# DigitalLabBoard_Stepper.net
KiCad netlist of a schematic drawn in Altium Designer
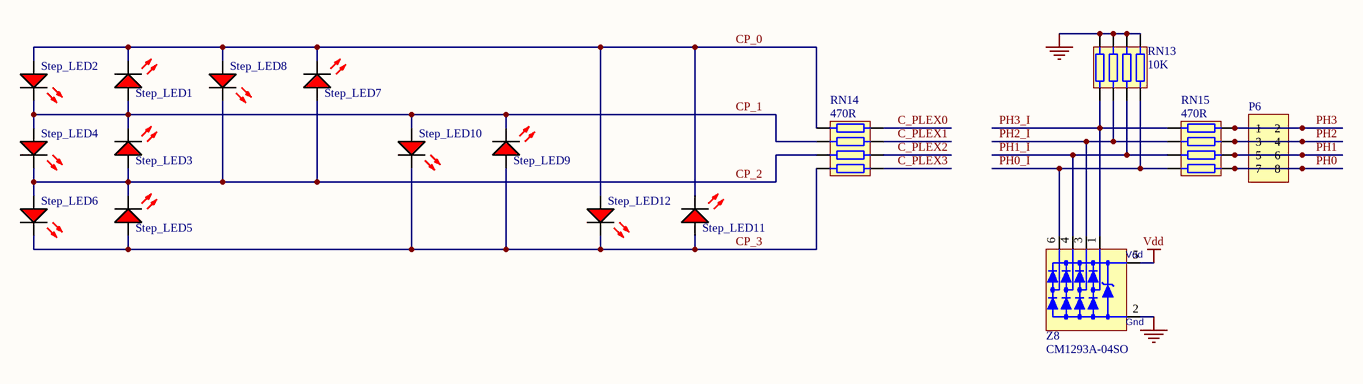
[diagram p0: DigitalLabBoard_Stepper.SchDoc]

(export (version "E")
  (design (tool "Eeschema 10.0.6"))
  (components
    (comp (ref "P6")
      (value "Header 2x4")
      (footprint "HDR2X4S")
      (libsource (lib "MyLibrary") (part "Header 2x4"))
    )
    (comp (ref "RN13")
      (value "10K")
      (footprint "CR1206-0603_X4_N")
      (description "SMT x4 Resistor Array")
      (libsource (lib "") (part "ResistorNetwork_CR0603x4_2"))
    )
    (comp (ref "RN14")
      (value "470R")
      (footprint "CR1206-0603_X4_N")
      (description "SMT x4 Resistor Array")
      (libsource (lib "") (part "ResistorNetwork_CR0603x4_1"))
    )
    (comp (ref "RN15")
      (value "470R")
      (footprint "CR1206-0603_X4_N")
      (description "SMT x4 Resistor Array")
      (libsource (lib "MyLibrary") (part "ResistorNetwork_CR0603x4"))
    )
    (comp (ref "Step_LED1")
      (value "LED Red")
      (footprint "LED1608-0603-RED")
      (description "LED 0603 Red")
      (fields (field (name "MANUFACTURER") "Generic Components") (field (name "PUBLISHER") "Altium Limited"))
      (libsource (lib "MySchLib") (part "LED-0603-Red"))
    )
    (comp (ref "Step_LED2")
      (value "LED Red")
      (footprint "LED1608-0603-RED")
      (description "LED 0603 Red")
      (fields (field (name "MANUFACTURER") "Generic Components") (field (name "PUBLISHER") "Altium Limited"))
      (libsource (lib "MySchLib") (part "LED-0603-Red"))
    )
    (comp (ref "Step_LED3")
      (value "LED Red")
      (footprint "LED1608-0603-RED")
      (description "LED 0603 Red")
      (fields (field (name "MANUFACTURER") "Generic Components") (field (name "PUBLISHER") "Altium Limited"))
      (libsource (lib "MySchLib") (part "LED-0603-Red"))
    )
    (comp (ref "Step_LED4")
      (value "LED Red")
      (footprint "LED1608-0603-RED")
      (description "LED 0603 Red")
      (fields (field (name "MANUFACTURER") "Generic Components") (field (name "PUBLISHER") "Altium Limited"))
      (libsource (lib "MySchLib") (part "LED-0603-Red"))
    )
    (comp (ref "Step_LED5")
      (value "LED Red")
      (footprint "LED1608-0603-RED")
      (description "LED 0603 Red")
      (fields (field (name "MANUFACTURER") "Generic Components") (field (name "PUBLISHER") "Altium Limited"))
      (libsource (lib "MySchLib") (part "LED-0603-Red"))
    )
    (comp (ref "Step_LED6")
      (value "LED Red")
      (footprint "LED1608-0603-RED")
      (description "LED 0603 Red")
      (fields (field (name "MANUFACTURER") "Generic Components") (field (name "PUBLISHER") "Altium Limited"))
      (libsource (lib "MySchLib") (part "LED-0603-Red"))
    )
    (comp (ref "Step_LED7")
      (value "LED Red")
      (footprint "LED1608-0603-RED")
      (description "LED 0603 Red")
      (fields (field (name "MANUFACTURER") "Generic Components") (field (name "PUBLISHER") "Altium Limited"))
      (libsource (lib "MySchLib") (part "LED-0603-Red"))
    )
    (comp (ref "Step_LED8")
      (value "LED Red")
      (footprint "LED1608-0603-RED")
      (description "LED 0603 Red")
      (fields (field (name "MANUFACTURER") "Generic Components") (field (name "PUBLISHER") "Altium Limited"))
      (libsource (lib "MySchLib") (part "LED-0603-Red"))
    )
    (comp (ref "Step_LED9")
      (value "LED Red")
      (footprint "LED1608-0603-RED")
      (description "LED 0603 Red")
      (fields (field (name "MANUFACTURER") "Generic Components") (field (name "PUBLISHER") "Altium Limited"))
      (libsource (lib "MySchLib") (part "LED-0603-Red"))
    )
    (comp (ref "Step_LED10")
      (value "LED Red")
      (footprint "LED1608-0603-RED")
      (description "LED 0603 Red")
      (fields (field (name "MANUFACTURER") "Generic Components") (field (name "PUBLISHER") "Altium Limited"))
      (libsource (lib "MySchLib") (part "LED-0603-Red"))
    )
    (comp (ref "Step_LED11")
      (value "LED Red")
      (footprint "LED1608-0603-RED")
      (description "LED 0603 Red")
      (fields (field (name "MANUFACTURER") "Generic Components") (field (name "PUBLISHER") "Altium Limited"))
      (libsource (lib "MySchLib") (part "LED-0603-Red"))
    )
    (comp (ref "Step_LED12")
      (value "LED Red")
      (footprint "LED1608-0603-RED")
      (description "LED 0603 Red")
      (fields (field (name "MANUFACTURER") "Generic Components") (field (name "PUBLISHER") "Altium Limited"))
      (libsource (lib "MySchLib") (part "LED-0603-Red"))
    )
    (comp (ref "Z8")
      (value "CM1293A-04SO")
      (footprint "SOT457_N")
      (description "Ultra low capacitance quadruple rail-to-rail ESD protection")
      (libsource (lib "MyLibrary") (part "CM1293A-04SO"))
    )
  )
  (nets
    (net (code "1") (name "/CP_0") (class "Default")
      (node (ref "RN14") (pin "5") (pinfunction "5_5") (pintype "passive"))
      (node (ref "Step_LED1") (pin "K") (pinfunction "K_K") (pintype "passive"))
      (node (ref "Step_LED11") (pin "K") (pinfunction "K_K") (pintype "passive"))
      (node (ref "Step_LED12") (pin "A") (pinfunction "A_A") (pintype "passive"))
      (node (ref "Step_LED2") (pin "A") (pinfunction "A_A") (pintype "passive"))
      (node (ref "Step_LED7") (pin "K") (pinfunction "K_K") (pintype "passive"))
      (node (ref "Step_LED8") (pin "A") (pinfunction "A_A") (pintype "passive"))
    )
    (net (code "2") (name "/CP_1") (class "Default")
      (node (ref "RN14") (pin "6") (pinfunction "6_6") (pintype "passive"))
      (node (ref "Step_LED1") (pin "A") (pinfunction "A_A") (pintype "passive"))
      (node (ref "Step_LED10") (pin "A") (pinfunction "A_A") (pintype "passive"))
      (node (ref "Step_LED2") (pin "K") (pinfunction "K_K") (pintype "passive"))
      (node (ref "Step_LED3") (pin "K") (pinfunction "K_K") (pintype "passive"))
      (node (ref "Step_LED4") (pin "A") (pinfunction "A_A") (pintype "passive"))
      (node (ref "Step_LED9") (pin "K") (pinfunction "K_K") (pintype "passive"))
    )
    (net (code "3") (name "/CP_2") (class "Default")
      (node (ref "RN14") (pin "7") (pinfunction "7_7") (pintype "passive"))
      (node (ref "Step_LED3") (pin "A") (pinfunction "A_A") (pintype "passive"))
      (node (ref "Step_LED4") (pin "K") (pinfunction "K_K") (pintype "passive"))
      (node (ref "Step_LED5") (pin "K") (pinfunction "K_K") (pintype "passive"))
      (node (ref "Step_LED6") (pin "A") (pinfunction "A_A") (pintype "passive"))
      (node (ref "Step_LED7") (pin "A") (pinfunction "A_A") (pintype "passive"))
      (node (ref "Step_LED8") (pin "K") (pinfunction "K_K") (pintype "passive"))
    )
    (net (code "4") (name "/CP_3") (class "Default")
      (node (ref "RN14") (pin "8") (pinfunction "8_8") (pintype "passive"))
      (node (ref "Step_LED10") (pin "K") (pinfunction "K_K") (pintype "passive"))
      (node (ref "Step_LED11") (pin "A") (pinfunction "A_A") (pintype "passive"))
      (node (ref "Step_LED12") (pin "K") (pinfunction "K_K") (pintype "passive"))
      (node (ref "Step_LED5") (pin "A") (pinfunction "A_A") (pintype "passive"))
      (node (ref "Step_LED6") (pin "K") (pinfunction "K_K") (pintype "passive"))
      (node (ref "Step_LED9") (pin "A") (pinfunction "A_A") (pintype "passive"))
    )
    (net (code "5") (name "/C_PLEX0") (class "Default")
      (node (ref "RN14") (pin "4") (pinfunction "4_4") (pintype "passive"))
    )
    (net (code "6") (name "/C_PLEX1") (class "Default")
      (node (ref "RN14") (pin "3") (pinfunction "3_3") (pintype "passive"))
    )
    (net (code "7") (name "/C_PLEX2") (class "Default")
      (node (ref "RN14") (pin "2") (pinfunction "2_2") (pintype "passive"))
    )
    (net (code "8") (name "/C_PLEX3") (class "Default")
      (node (ref "RN14") (pin "1") (pinfunction "1_1") (pintype "passive"))
    )
    (net (code "9") (name "/PH0") (class "Default")
      (node (ref "P6") (pin "7") (pinfunction "7_7") (pintype "passive"))
      (node (ref "P6") (pin "8") (pinfunction "8_8") (pintype "passive"))
      (node (ref "RN15") (pin "8") (pinfunction "8_8") (pintype "passive"))
    )
    (net (code "10") (name "/PH0_I") (class "Default")
      (node (ref "RN13") (pin "8") (pinfunction "8_8") (pintype "passive"))
      (node (ref "RN15") (pin "1") (pinfunction "1_1") (pintype "passive"))
      (node (ref "Z8") (pin "6") (pintype "passive"))
    )
    (net (code "11") (name "/PH1") (class "Default")
      (node (ref "P6") (pin "5") (pinfunction "5_5") (pintype "passive"))
      (node (ref "P6") (pin "6") (pinfunction "6_6") (pintype "passive"))
      (node (ref "RN15") (pin "7") (pinfunction "7_7") (pintype "passive"))
    )
    (net (code "12") (name "/PH1_I") (class "Default")
      (node (ref "RN13") (pin "7") (pinfunction "7_7") (pintype "passive"))
      (node (ref "RN15") (pin "2") (pinfunction "2_2") (pintype "passive"))
      (node (ref "Z8") (pin "4") (pintype "passive"))
    )
    (net (code "13") (name "/PH2") (class "Default")
      (node (ref "P6") (pin "3") (pinfunction "3_3") (pintype "passive"))
      (node (ref "P6") (pin "4") (pinfunction "4_4") (pintype "passive"))
      (node (ref "RN15") (pin "6") (pinfunction "6_6") (pintype "passive"))
    )
    (net (code "14") (name "/PH2_I") (class "Default")
      (node (ref "RN13") (pin "6") (pinfunction "6_6") (pintype "passive"))
      (node (ref "RN15") (pin "3") (pinfunction "3_3") (pintype "passive"))
      (node (ref "Z8") (pin "3") (pintype "passive"))
    )
    (net (code "15") (name "/PH3") (class "Default")
      (node (ref "P6") (pin "1") (pinfunction "1_1") (pintype "passive"))
      (node (ref "P6") (pin "2") (pinfunction "2_2") (pintype "passive"))
      (node (ref "RN15") (pin "5") (pinfunction "5_5") (pintype "passive"))
    )
    (net (code "16") (name "/PH3_I") (class "Default")
      (node (ref "RN13") (pin "5") (pinfunction "5_5") (pintype "passive"))
      (node (ref "RN15") (pin "4") (pinfunction "4_4") (pintype "passive"))
      (node (ref "Z8") (pin "1") (pintype "passive"))
    )
    (net (code "17") (name "GND") (class "Default")
      (node (ref "RN13") (pin "1") (pinfunction "1_1") (pintype "passive"))
      (node (ref "RN13") (pin "2") (pinfunction "2_2") (pintype "passive"))
      (node (ref "RN13") (pin "3") (pinfunction "3_3") (pintype "passive"))
      (node (ref "RN13") (pin "4") (pinfunction "4_4") (pintype "passive"))
      (node (ref "Z8") (pin "2") (pinfunction "Vn_2") (pintype "passive"))
    )
    (net (code "18") (name "Vdd") (class "Default")
      (node (ref "Z8") (pin "5") (pinfunction "Vp_5") (pintype "passive"))
    )
  )
)
